# design.net
KiCad netlist of a schematic drawn in Altium Designer
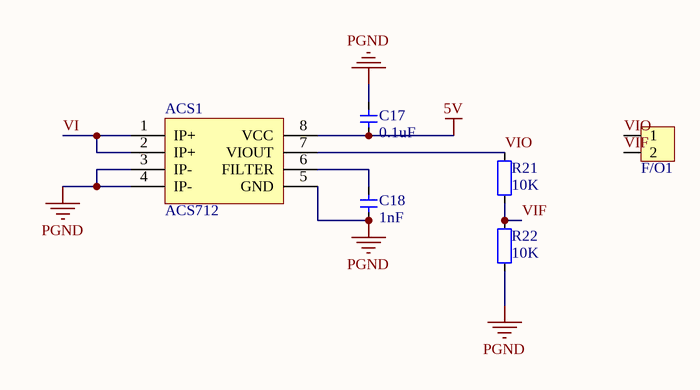
[diagram p0: 电流环.SchDoc]

(export (version "E")
  (design (tool "Eeschema 10.0.6"))
  (components
    (comp (ref "ACS1")
      (value "ACS712")
      (footprint "SOP8ACS712")
      (description "Sensor Current")
      (libsource (lib "SCH_IntegratedCircuit") (part "ACS712"))
    )
    (comp (ref "C17")
      (value "0.1uF")
      (footprint "CAP_0603")
      (description "Capacitor")
      (fields (field (name "Comment") "Cap_0603"))
      (libsource (lib "Integrated_Library") (part "Cap_0603"))
    )
    (comp (ref "C18")
      (value "1nF")
      (footprint "PCB_PassiveCap:CAP_0603")
      (description "Capacitor")
      (fields (field (name "Comment") "Cap_0603"))
      (libsource (lib "SCH_Passive") (part "Cap_0603"))
    )
    (comp (ref "F/O1")
      (value "HDR1x2_2.54")
      (footprint "HDR1X2_2.54_180")
      (description "Header")
      (libsource (lib "Integrated_Library") (part "HDR1x2_2.54"))
    )
    (comp (ref "R21")
      (value "10K")
      (footprint "RES_0603")
      (description "Resistor")
      (fields (field (name "Comment") "Res_0603"))
      (libsource (lib "Integrated_Library") (part "Res_0603"))
    )
    (comp (ref "R22")
      (value "10K")
      (footprint "RES_0603")
      (description "Resistor")
      (fields (field (name "Comment") "Res_0603"))
      (libsource (lib "Integrated_Library") (part "Res_0603"))
    )
  )
  (nets
    (net (code "1") (name "/VI") (class "Default")
      (node (ref "ACS1") (pin "1") (pinfunction "IP+_1") (pintype "passive"))
      (node (ref "ACS1") (pin "2") (pinfunction "IP+_2") (pintype "passive"))
    )
    (net (code "2") (name "/VIF") (class "Default")
      (node (ref "F/O1") (pin "2") (pinfunction "2_2") (pintype "passive"))
      (node (ref "R21") (pin "2") (pinfunction "2_2") (pintype "passive"))
      (node (ref "R22") (pin "1") (pinfunction "1_1") (pintype "passive"))
    )
    (net (code "3") (name "/VIO") (class "Default")
      (node (ref "ACS1") (pin "7") (pinfunction "VIOUT_7") (pintype "passive"))
      (node (ref "F/O1") (pin "1") (pinfunction "1_1") (pintype "passive"))
      (node (ref "R21") (pin "1") (pinfunction "1_1") (pintype "passive"))
    )
    (net (code "4") (name "5V") (class "Default")
      (node (ref "ACS1") (pin "8") (pinfunction "VCC_8") (pintype "passive"))
      (node (ref "C17") (pin "1") (pinfunction "1_1") (pintype "passive"))
    )
    (net (code "5") (name "Net-(ACS1-FILTER)") (class "Default")
      (node (ref "ACS1") (pin "6") (pinfunction "FILTER_6") (pintype "passive"))
      (node (ref "C18") (pin "2") (pinfunction "2_2") (pintype "passive"))
    )
    (net (code "6") (name "PGND") (class "Default")
      (node (ref "ACS1") (pin "3") (pinfunction "IP-_3") (pintype "passive"))
      (node (ref "ACS1") (pin "4") (pinfunction "IP-_4") (pintype "passive"))
      (node (ref "ACS1") (pin "5") (pinfunction "GND_5") (pintype "passive"))
      (node (ref "C17") (pin "2") (pinfunction "2_2") (pintype "passive"))
      (node (ref "C18") (pin "1") (pinfunction "1_1") (pintype "passive"))
      (node (ref "R22") (pin "2") (pinfunction "2_2") (pintype "passive"))
    )
  )
)
